# 14-DPLL_1.net
KiCad netlist of a schematic drawn in Altium Designer
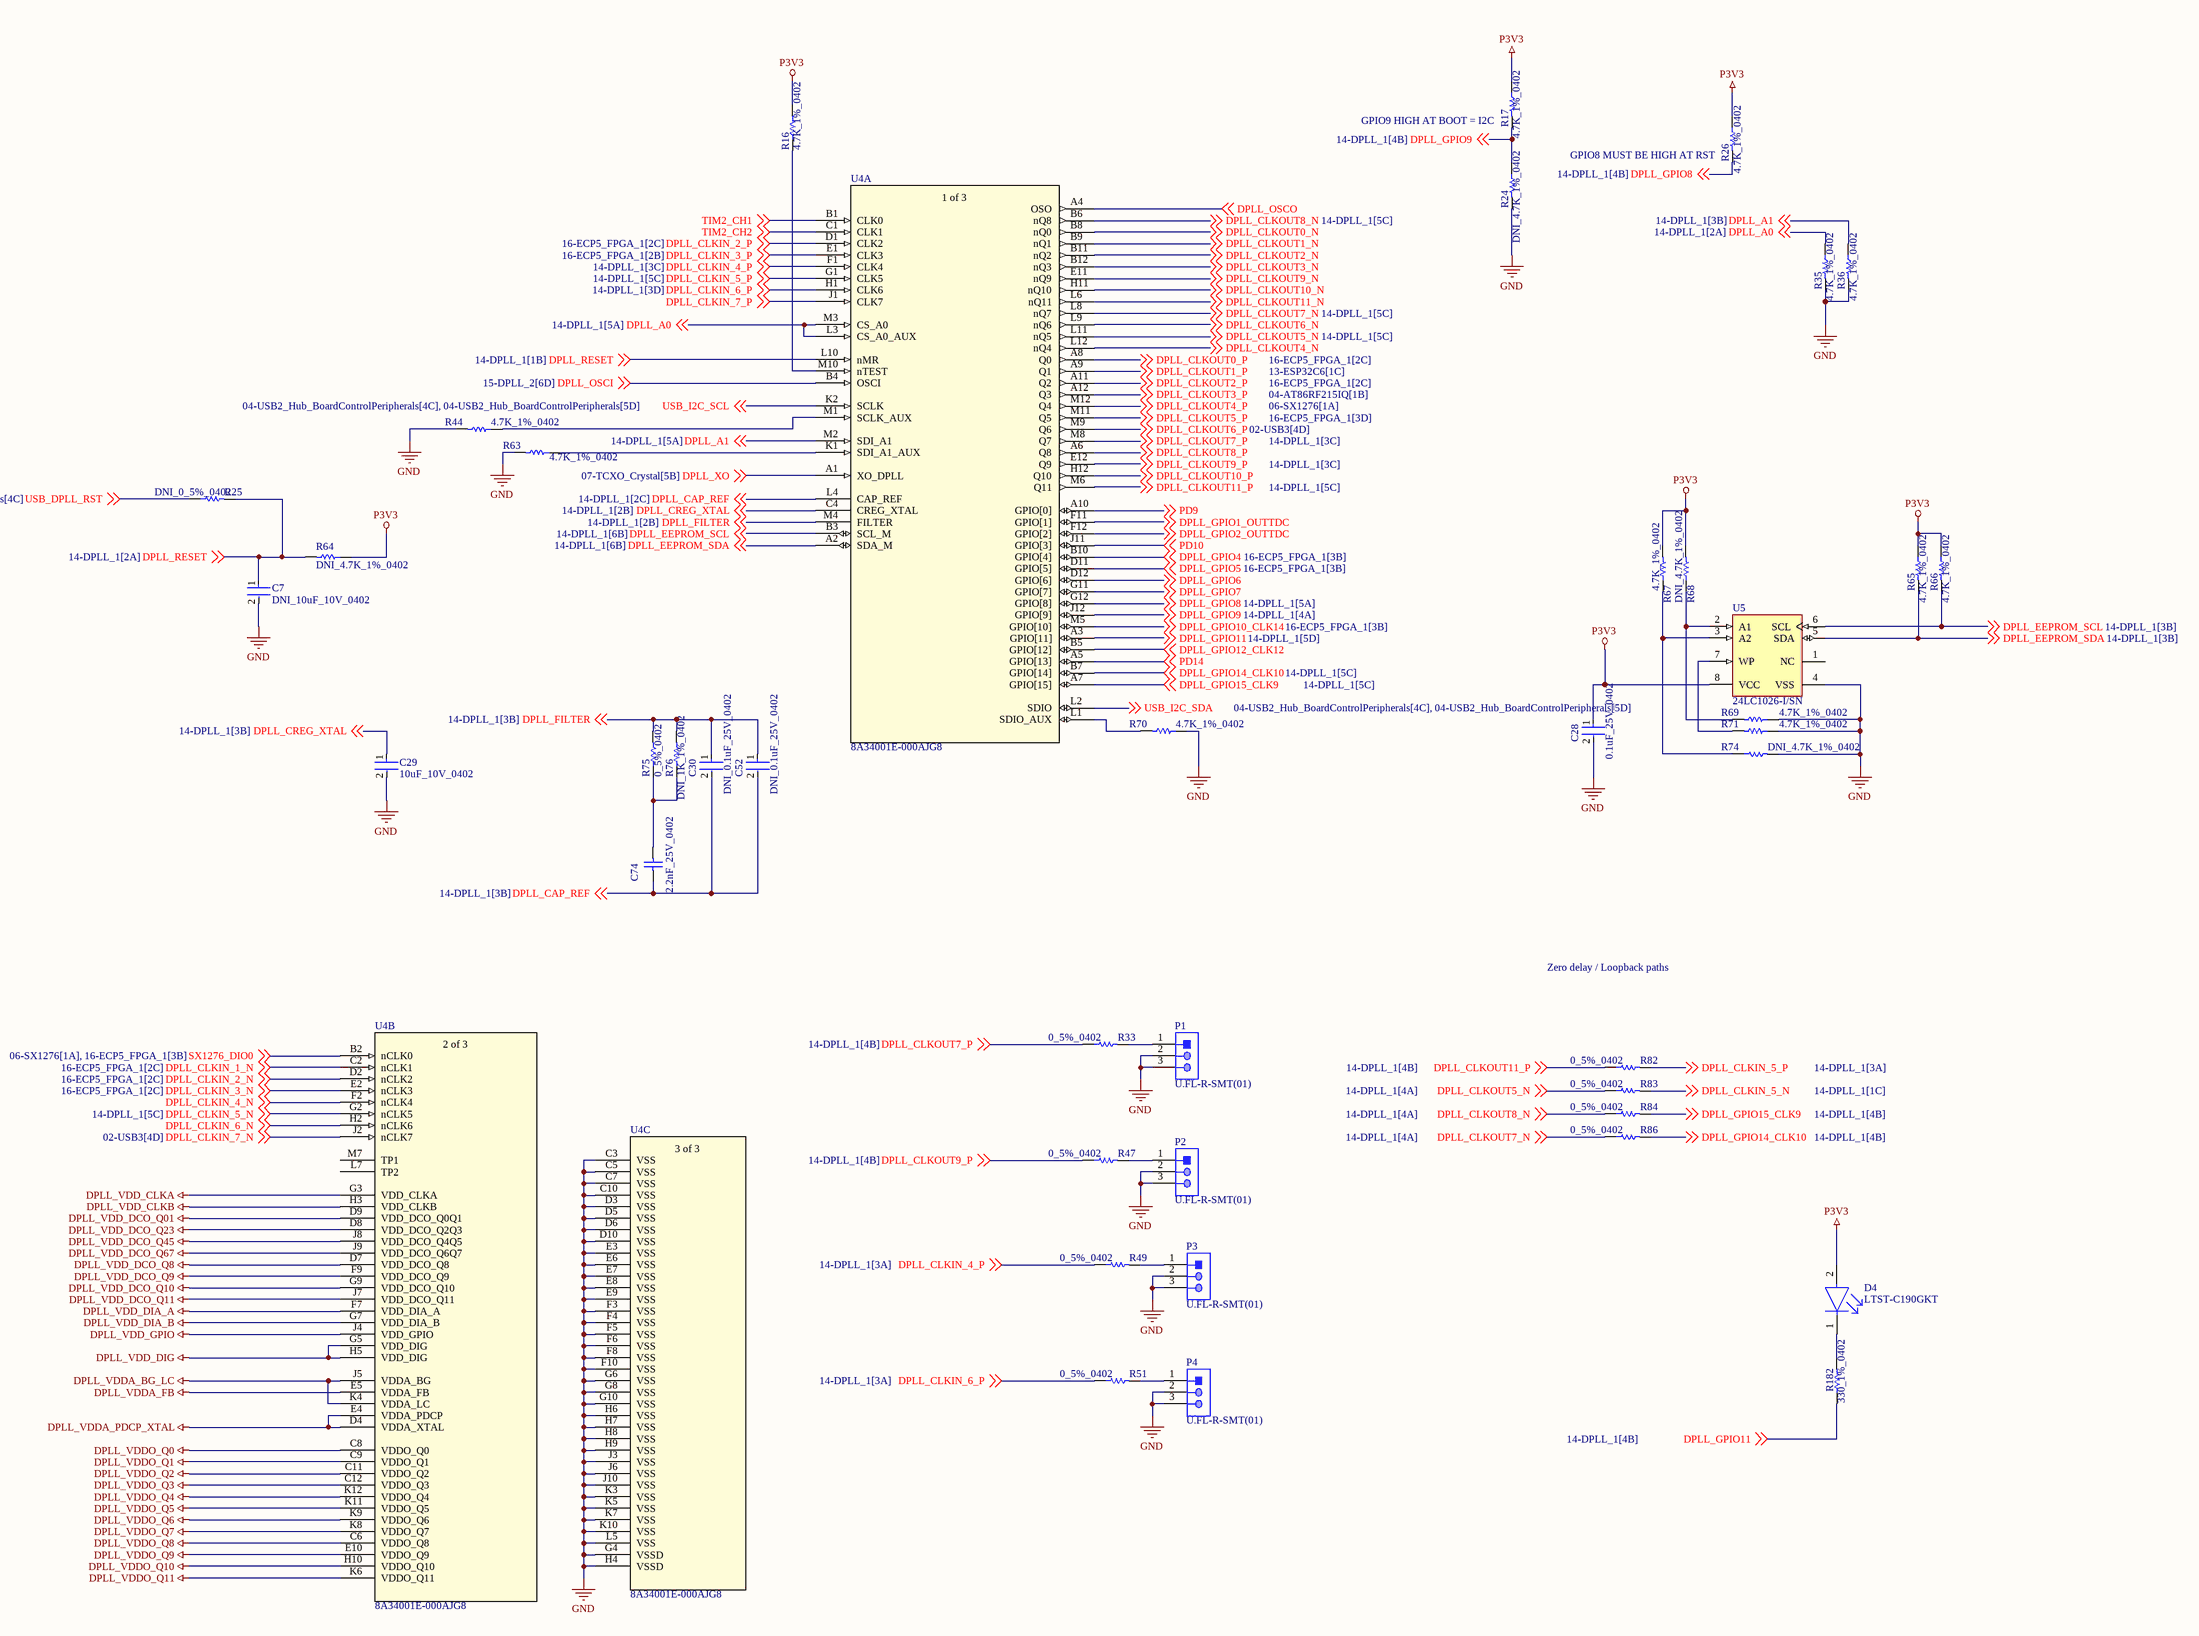
[diagram p0: 14-DPLL_1.SchDoc]

(export (version "E")
  (design (tool "Eeschema 10.0.6"))
  (components
    (comp (ref "C7")
      (value "DNI_10uF_10V_0402")
      (footprint "FP-CL05A106MP5NUNC-MFG")
      (description "CAP CER 10UF 10V X5R 0402")
      (fields
        (field (name "OCTOPART") "https://octopart.com/cl05a106mp5nunc-samsung-22457395")
        (field (name "TOLERANCE") "20%")
      )
      (libsource (lib "Altium Content Vault") (part "b4654b650e69147ec39a6b967a45e02"))
    )
    (comp (ref "C28")
      (value "0.1uF_25V_0402")
      (footprint "FP-0402-L_1_0_1-W_0_5_0_1-IPC_C")
      (description "General Purpose Ceramic Capacitor, 0402, 100nF, 10%, X7R, 15%, 25V")
      (fields (field (name "VOLTAGE") "25V") (field (name "TOLERANCE") "10%"))
      (libsource (lib "Altium Content Vault") (part "b4654b650e69147ec39a6b967a45e02"))
    )
    (comp (ref "C29")
      (value "10uF_10V_0402")
      (footprint "FP-CL05A106MP5NUNC-MFG")
      (description "CAP CER 10UF 10V X5R 0402")
      (fields
        (field (name "OCTOPART") "https://octopart.com/cl05a106mp5nunc-samsung-22457395")
        (field (name "TOLERANCE") "20%")
      )
      (libsource (lib "Altium Content Vault") (part "b4654b650e69147ec39a6b967a45e02"))
    )
    (comp (ref "C30")
      (value "DNI_0.1uF_25V_0402")
      (footprint "FP-0402-L_1_0_1-W_0_5_0_1-IPC_C")
      (description "General Purpose Ceramic Capacitor, 0402, 100nF, 10%, X7R, 15%, 25V")
      (fields (field (name "VOLTAGE") "25V") (field (name "TOLERANCE") "10%"))
      (libsource (lib "Altium Content Vault") (part "b4654b650e69147ec39a6b967a45e02"))
    )
    (comp (ref "C52")
      (value "DNI_0.1uF_25V_0402")
      (footprint "FP-0402-L_1_0_1-W_0_5_0_1-IPC_C")
      (description "General Purpose Ceramic Capacitor, 0402, 100nF, 10%, X7R, 15%, 25V")
      (fields (field (name "VOLTAGE") "25V") (field (name "TOLERANCE") "10%"))
      (libsource (lib "Altium Content Vault") (part "b4654b650e69147ec39a6b967a45e02"))
    )
    (comp (ref "C74")
      (value "2.2nF_25V_0402")
      (footprint "CAPC1005X56X25LL10T15")
      (fields
        (field (name "MANUFACTURER") "AVX Interconnect / Elco")
        (field (name "PART NUMBER") "04025C222JAT2A")
      )
      (libsource (lib "Altium Content Vault") (part "CAP"))
    )
    (comp (ref "D4")
      (value "LTST-C190GKT")
      (footprint "FP-LTST-C190GKT-MFG")
      (description "LED GREEN CLEAR CHIP SMD")
      (fields (field (name "VOLTAGE") "2V"))
      (libsource (lib "Altium Content Vault") (part "8706943c75ba83719d021d2fdc84c58"))
    )
    (comp (ref "P1")
      (value "U.FL-R-SMT(01)")
      (footprint "HRS-U.FL-R-SMT(10)_V")
      (description "CONN RECPT ULTRA-MINI COAX SMD")
      (fields (field (name "MANUFACTURER") "Hirose Electric") (field (name "APPROVAL CATEGORY") "UL94V-0"))
      (libsource (lib "Altium Content Vault") (part "CN-1P-M-R3"))
    )
    (comp (ref "P2")
      (value "U.FL-R-SMT(01)")
      (footprint "HRS-U.FL-R-SMT(10)_V")
      (description "CONN RECPT ULTRA-MINI COAX SMD")
      (fields (field (name "MANUFACTURER") "Hirose Electric") (field (name "APPROVAL CATEGORY") "UL94V-0"))
      (libsource (lib "Altium Content Vault") (part "CN-1P-M-R3"))
    )
    (comp (ref "P3")
      (value "U.FL-R-SMT(01)")
      (footprint "HRS-U.FL-R-SMT(10)_V")
      (description "CONN RECPT ULTRA-MINI COAX SMD")
      (fields (field (name "MANUFACTURER") "Hirose Electric") (field (name "APPROVAL CATEGORY") "UL94V-0"))
      (libsource (lib "Altium Content Vault") (part "CN-1P-M-R3"))
    )
    (comp (ref "P4")
      (value "U.FL-R-SMT(01)")
      (footprint "HRS-U.FL-R-SMT(10)_V")
      (description "CONN RECPT ULTRA-MINI COAX SMD")
      (fields (field (name "MANUFACTURER") "Hirose Electric") (field (name "APPROVAL CATEGORY") "UL94V-0"))
      (libsource (lib "Altium Content Vault") (part "CN-1P-M-R3"))
    )
    (comp (ref "R16")
      (value "4.7K_1%_0402")
      (footprint "RESC1005X40X25NL10T10")
      (fields (field (name "MANUFACTURER") "Bourns") (field (name "PART NUMBER") "CR0402-FX-4701GLF"))
      (libsource (lib "Altium Content Vault") (part "RES"))
    )
    (comp (ref "R17")
      (value "4.7K_1%_0402")
      (footprint "RESC1005X40X25NL10T10")
      (fields (field (name "MANUFACTURER") "Bourns") (field (name "PART NUMBER") "CR0402-FX-4701GLF"))
      (libsource (lib "Altium Content Vault") (part "RES"))
    )
    (comp (ref "R24")
      (value "DNI_4.7K_1%_0402")
      (footprint "RESC1005X40X25NL10T10")
      (fields (field (name "MANUFACTURER") "Bourns") (field (name "PART NUMBER") "CR0402-FX-4701GLF"))
      (libsource (lib "Altium Content Vault") (part "RES"))
    )
    (comp (ref "R25")
      (value "DNI_0_5%_0402")
      (footprint "RESC1005X40X25LL10T10")
      (fields (field (name "MANUFACTURER") "KOA Speer") (field (name "PART NUMBER") "RK73Z1ETTP"))
      (libsource (lib "Altium Content Vault") (part "RES"))
    )
    (comp (ref "R26")
      (value "4.7K_1%_0402")
      (footprint "RESC1005X40X25NL10T10")
      (fields (field (name "MANUFACTURER") "Bourns") (field (name "PART NUMBER") "CR0402-FX-4701GLF"))
      (libsource (lib "Altium Content Vault") (part "RES"))
    )
    (comp (ref "R33")
      (value "0_5%_0402")
      (footprint "RESC1005X40X25LL10T10")
      (fields (field (name "MANUFACTURER") "KOA Speer") (field (name "PART NUMBER") "RK73Z1ETTP"))
      (libsource (lib "Altium Content Vault") (part "RES"))
    )
    (comp (ref "R35")
      (value "4.7K_1%_0402")
      (footprint "RESC1005X40X25NL10T10")
      (fields (field (name "MANUFACTURER") "Bourns") (field (name "PART NUMBER") "CR0402-FX-4701GLF"))
      (libsource (lib "Altium Content Vault") (part "RES"))
    )
    (comp (ref "R36")
      (value "4.7K_1%_0402")
      (footprint "RESC1005X40X25NL10T10")
      (fields (field (name "MANUFACTURER") "Bourns") (field (name "PART NUMBER") "CR0402-FX-4701GLF"))
      (libsource (lib "Altium Content Vault") (part "RES"))
    )
    (comp (ref "R44")
      (value "4.7K_1%_0402")
      (footprint "RESC1005X40X25NL10T10")
      (fields (field (name "MANUFACTURER") "Bourns") (field (name "PART NUMBER") "CR0402-FX-4701GLF"))
      (libsource (lib "Altium Content Vault") (part "RES"))
    )
    (comp (ref "R47")
      (value "0_5%_0402")
      (footprint "RESC1005X40X25LL10T10")
      (fields (field (name "MANUFACTURER") "KOA Speer") (field (name "PART NUMBER") "RK73Z1ETTP"))
      (libsource (lib "Altium Content Vault") (part "RES"))
    )
    (comp (ref "R49")
      (value "0_5%_0402")
      (footprint "RESC1005X40X25LL10T10")
      (fields (field (name "MANUFACTURER") "KOA Speer") (field (name "PART NUMBER") "RK73Z1ETTP"))
      (libsource (lib "Altium Content Vault") (part "RES"))
    )
    (comp (ref "R51")
      (value "0_5%_0402")
      (footprint "RESC1005X40X25LL10T10")
      (fields (field (name "MANUFACTURER") "KOA Speer") (field (name "PART NUMBER") "RK73Z1ETTP"))
      (libsource (lib "Altium Content Vault") (part "RES"))
    )
    (comp (ref "R63")
      (value "4.7K_1%_0402")
      (footprint "RESC1005X40X25NL10T10")
      (fields (field (name "MANUFACTURER") "Bourns") (field (name "PART NUMBER") "CR0402-FX-4701GLF"))
      (libsource (lib "Altium Content Vault") (part "RES"))
    )
    (comp (ref "R64")
      (value "DNI_4.7K_1%_0402")
      (footprint "RESC1005X40X25NL10T10")
      (fields (field (name "MANUFACTURER") "Bourns") (field (name "PART NUMBER") "CR0402-FX-4701GLF"))
      (libsource (lib "Altium Content Vault") (part "RES"))
    )
    (comp (ref "R65")
      (value "4.7K_1%_0402")
      (footprint "RESC1005X40X25NL10T10")
      (fields (field (name "MANUFACTURER") "Bourns") (field (name "PART NUMBER") "CR0402-FX-4701GLF"))
      (libsource (lib "Altium Content Vault") (part "RES"))
    )
    (comp (ref "R66")
      (value "4.7K_1%_0402")
      (footprint "RESC1005X40X25NL10T10")
      (fields (field (name "MANUFACTURER") "Bourns") (field (name "PART NUMBER") "CR0402-FX-4701GLF"))
      (libsource (lib "Altium Content Vault") (part "RES"))
    )
    (comp (ref "R67")
      (value "4.7K_1%_0402")
      (footprint "RESC1005X40X25NL10T10")
      (fields (field (name "MANUFACTURER") "Bourns") (field (name "PART NUMBER") "CR0402-FX-4701GLF"))
      (libsource (lib "Altium Content Vault") (part "RES"))
    )
    (comp (ref "R68")
      (value "DNI_4.7K_1%_0402")
      (footprint "RESC1005X40X25NL10T10")
      (fields (field (name "MANUFACTURER") "Bourns") (field (name "PART NUMBER") "CR0402-FX-4701GLF"))
      (libsource (lib "Altium Content Vault") (part "RES"))
    )
    (comp (ref "R69")
      (value "4.7K_1%_0402")
      (footprint "RESC1005X40X25NL10T10")
      (fields (field (name "MANUFACTURER") "Bourns") (field (name "PART NUMBER") "CR0402-FX-4701GLF"))
      (libsource (lib "Altium Content Vault") (part "RES"))
    )
    (comp (ref "R70")
      (value "4.7K_1%_0402")
      (footprint "RESC1005X40X25NL10T10")
      (fields (field (name "MANUFACTURER") "Bourns") (field (name "PART NUMBER") "CR0402-FX-4701GLF"))
      (libsource (lib "Altium Content Vault") (part "RES"))
    )
    (comp (ref "R71")
      (value "4.7K_1%_0402")
      (footprint "RESC1005X40X25NL10T10")
      (fields (field (name "MANUFACTURER") "Bourns") (field (name "PART NUMBER") "CR0402-FX-4701GLF"))
      (libsource (lib "Altium Content Vault") (part "RES"))
    )
    (comp (ref "R74")
      (value "DNI_4.7K_1%_0402")
      (footprint "RESC1005X40X25NL10T10")
      (fields (field (name "MANUFACTURER") "Bourns") (field (name "PART NUMBER") "CR0402-FX-4701GLF"))
      (libsource (lib "Altium Content Vault") (part "RES"))
    )
    (comp (ref "R75")
      (value "0_5%_0402")
      (footprint "RESC1005X40X25LL10T10")
      (fields (field (name "MANUFACTURER") "KOA Speer") (field (name "PART NUMBER") "RK73Z1ETTP"))
      (libsource (lib "Altium Content Vault") (part "RES"))
    )
    (comp (ref "R76")
      (value "DNI_1K_1%_0402")
      (footprint "RESC1005X40X25NL05T05")
      (fields (field (name "MANUFACTURER") "Vishay Dale") (field (name "PART NUMBER") "CRCW04021K00FKTD"))
      (libsource (lib "Altium Content Vault") (part "RES"))
    )
    (comp (ref "R82")
      (value "0_5%_0402")
      (footprint "RESC1005X40X25LL10T10")
      (fields (field (name "MANUFACTURER") "KOA Speer") (field (name "PART NUMBER") "RK73Z1ETTP"))
      (libsource (lib "Altium Content Vault") (part "RES"))
    )
    (comp (ref "R83")
      (value "0_5%_0402")
      (footprint "RESC1005X40X25LL10T10")
      (fields (field (name "MANUFACTURER") "KOA Speer") (field (name "PART NUMBER") "RK73Z1ETTP"))
      (libsource (lib "Altium Content Vault") (part "RES"))
    )
    (comp (ref "R84")
      (value "0_5%_0402")
      (footprint "RESC1005X40X25LL10T10")
      (fields (field (name "MANUFACTURER") "KOA Speer") (field (name "PART NUMBER") "RK73Z1ETTP"))
      (libsource (lib "Altium Content Vault") (part "RES"))
    )
    (comp (ref "R86")
      (value "0_5%_0402")
      (footprint "RESC1005X40X25LL10T10")
      (fields (field (name "MANUFACTURER") "KOA Speer") (field (name "PART NUMBER") "RK73Z1ETTP"))
      (libsource (lib "Altium Content Vault") (part "RES"))
    )
    (comp (ref "R182")
      (value "330_1%_0402")
      (footprint "RESC1005X40X25NL10T10")
      (fields (field (name "MANUFACTURER") "Panasonic") (field (name "PART NUMBER") "ERA-2AED331X"))
      (libsource (lib "Altium Content Vault") (part "RES"))
    )
    (comp (ref "U4")
      (value "8A34001E-000AJG8")
      (footprint "144-CABGA_REN")
      (description "No Description Available")
      (fields (field (name "COPYRIGHT") "Copyright (C) 2024 Ultra Librarian. All rights reserved."))
      (libsource (lib "8A34001E-000AJG8") (part "8A34001E-000AJG8"))
    )
    (comp (ref "U5")
      (value "24LC1026-I/SN")
      (footprint "MCHP-SOIC-SN8_N")
      (description "1024K bits I2C™ Serial EEPROM, 2.5 to 5.5 V, 400 kHz, -40 to 85 degC, 8-pin SOIC (SN8), Tube")
      (fields (field (name "MANUFACTURER") "Microchip"))
      (libsource (lib "Altium Content Vault") (part "MCHP-24LC1026-SOIC-8"))
    )
  )
  (nets
    (net (code "1") (name "DPLL_A0") (class "Default")
      (node (ref "R35") (pin "1") (pinfunction "1_1") (pintype "passive"))
      (node (ref "U4") (pin "L3") (pinfunction "CS_A0_AUX_L3") (pintype "input"))
      (node (ref "U4") (pin "M3") (pinfunction "CS_A0_M3") (pintype "input"))
    )
    (net (code "2") (name "DPLL_A1") (class "Default")
      (node (ref "R36") (pin "1") (pinfunction "1_1") (pintype "passive"))
      (node (ref "U4") (pin "M2") (pinfunction "SDI_A1_M2") (pintype "input"))
    )
    (net (code "3") (name "DPLL_CAP_REF") (class "Default")
      (node (ref "C30") (pin "2") (pinfunction "2_2") (pintype "passive"))
      (node (ref "C52") (pin "2") (pinfunction "2_2") (pintype "passive"))
      (node (ref "C74") (pin "1") (pinfunction "1_1") (pintype "passive"))
      (node (ref "U4") (pin "L4") (pinfunction "CAP_REF_L4") (pintype "passive"))
    )
    (net (code "4") (name "DPLL_CLKIN_1_N") (class "Default")
      (node (ref "U4") (pin "C2") (pinfunction "nCLK1_C2") (pintype "input"))
    )
    (net (code "5") (name "DPLL_CLKIN_2_N") (class "Default")
      (node (ref "U4") (pin "D2") (pinfunction "nCLK2_D2") (pintype "input"))
    )
    (net (code "6") (name "DPLL_CLKIN_2_P") (class "Default")
      (node (ref "U4") (pin "D1") (pinfunction "CLK2_D1") (pintype "input"))
    )
    (net (code "7") (name "DPLL_CLKIN_3_N") (class "Default")
      (node (ref "U4") (pin "E2") (pinfunction "nCLK3_E2") (pintype "input"))
    )
    (net (code "8") (name "DPLL_CLKIN_3_P") (class "Default")
      (node (ref "U4") (pin "E1") (pinfunction "CLK3_E1") (pintype "input"))
    )
    (net (code "9") (name "DPLL_CLKIN_4_N") (class "Default")
      (node (ref "U4") (pin "F2") (pinfunction "nCLK4_F2") (pintype "input"))
    )
    (net (code "10") (name "DPLL_CLKIN_4_P") (class "Default")
      (node (ref "R49") (pin "1") (pinfunction "1_1") (pintype "passive"))
      (node (ref "U4") (pin "F1") (pinfunction "CLK4_F1") (pintype "input"))
    )
    (net (code "11") (name "DPLL_CLKIN_5_N") (class "Default")
      (node (ref "R83") (pin "2") (pinfunction "2_2") (pintype "passive"))
      (node (ref "U4") (pin "G2") (pinfunction "nCLK5_G2") (pintype "input"))
    )
    (net (code "12") (name "DPLL_CLKIN_5_P") (class "Default")
      (node (ref "R82") (pin "2") (pinfunction "2_2") (pintype "passive"))
      (node (ref "U4") (pin "G1") (pinfunction "CLK5_G1") (pintype "input"))
    )
    (net (code "13") (name "DPLL_CLKIN_6_N") (class "Default")
      (node (ref "U4") (pin "H2") (pinfunction "nCLK6_H2") (pintype "input"))
    )
    (net (code "14") (name "DPLL_CLKIN_6_P") (class "Default")
      (node (ref "R51") (pin "1") (pinfunction "1_1") (pintype "passive"))
      (node (ref "U4") (pin "H1") (pinfunction "CLK6_H1") (pintype "input"))
    )
    (net (code "15") (name "DPLL_CLKIN_7_N") (class "Default")
      (node (ref "U4") (pin "J2") (pinfunction "nCLK7_J2") (pintype "input"))
    )
    (net (code "16") (name "DPLL_CLKIN_7_P") (class "Default")
      (node (ref "U4") (pin "J1") (pinfunction "CLK7_J1") (pintype "input"))
    )
    (net (code "17") (name "DPLL_CLKOUT0_N") (class "Default")
      (node (ref "U4") (pin "B8") (pinfunction "nQ0_B8") (pintype "output"))
    )
    (net (code "18") (name "DPLL_CLKOUT0_P") (class "Default")
      (node (ref "U4") (pin "A8") (pinfunction "Q0_A8") (pintype "output"))
    )
    (net (code "19") (name "DPLL_CLKOUT1_N") (class "Default")
      (node (ref "U4") (pin "B9") (pinfunction "nQ1_B9") (pintype "output"))
    )
    (net (code "20") (name "DPLL_CLKOUT1_P") (class "Default")
      (node (ref "U4") (pin "A9") (pinfunction "Q1_A9") (pintype "output"))
    )
    (net (code "21") (name "DPLL_CLKOUT2_N") (class "Default")
      (node (ref "U4") (pin "B11") (pinfunction "nQ2_B11") (pintype "output"))
    )
    (net (code "22") (name "DPLL_CLKOUT2_P") (class "Default")
      (node (ref "U4") (pin "A11") (pinfunction "Q2_A11") (pintype "output"))
    )
    (net (code "23") (name "DPLL_CLKOUT3_N") (class "Default")
      (node (ref "U4") (pin "B12") (pinfunction "nQ3_B12") (pintype "output"))
    )
    (net (code "24") (name "DPLL_CLKOUT3_P") (class "Default")
      (node (ref "U4") (pin "A12") (pinfunction "Q3_A12") (pintype "output"))
    )
    (net (code "25") (name "DPLL_CLKOUT4_N") (class "Default")
      (node (ref "U4") (pin "L12") (pinfunction "nQ4_L12") (pintype "output"))
    )
    (net (code "26") (name "DPLL_CLKOUT4_P") (class "Default")
      (node (ref "U4") (pin "M12") (pinfunction "Q4_M12") (pintype "output"))
    )
    (net (code "27") (name "DPLL_CLKOUT5_N") (class "Default")
      (node (ref "R83") (pin "1") (pinfunction "1_1") (pintype "passive"))
      (node (ref "U4") (pin "L11") (pinfunction "nQ5_L11") (pintype "output"))
    )
    (net (code "28") (name "DPLL_CLKOUT5_P") (class "Default")
      (node (ref "U4") (pin "M11") (pinfunction "Q5_M11") (pintype "output"))
    )
    (net (code "29") (name "DPLL_CLKOUT6_N") (class "Default")
      (node (ref "U4") (pin "L9") (pinfunction "nQ6_L9") (pintype "output"))
    )
    (net (code "30") (name "DPLL_CLKOUT6_P") (class "Default")
      (node (ref "U4") (pin "M9") (pinfunction "Q6_M9") (pintype "output"))
    )
    (net (code "31") (name "DPLL_CLKOUT7_N") (class "Default")
      (node (ref "R86") (pin "1") (pinfunction "1_1") (pintype "passive"))
      (node (ref "U4") (pin "L8") (pinfunction "nQ7_L8") (pintype "output"))
    )
    (net (code "32") (name "DPLL_CLKOUT7_P") (class "Default")
      (node (ref "R33") (pin "1") (pinfunction "1_1") (pintype "passive"))
      (node (ref "U4") (pin "M8") (pinfunction "Q7_M8") (pintype "output"))
    )
    (net (code "33") (name "DPLL_CLKOUT8_N") (class "Default")
      (node (ref "R84") (pin "1") (pinfunction "1_1") (pintype "passive"))
      (node (ref "U4") (pin "B6") (pinfunction "nQ8_B6") (pintype "output"))
    )
    (net (code "34") (name "DPLL_CLKOUT8_P") (class "Default")
      (node (ref "U4") (pin "A6") (pinfunction "Q8_A6") (pintype "output"))
    )
    (net (code "35") (name "DPLL_CLKOUT9_N") (class "Default")
      (node (ref "U4") (pin "E11") (pinfunction "nQ9_E11") (pintype "output"))
    )
    (net (code "36") (name "DPLL_CLKOUT9_P") (class "Default")
      (node (ref "R47") (pin "1") (pinfunction "1_1") (pintype "passive"))
      (node (ref "U4") (pin "E12") (pinfunction "Q9_E12") (pintype "output"))
    )
    (net (code "37") (name "DPLL_CLKOUT10_N") (class "Default")
      (node (ref "U4") (pin "H11") (pinfunction "nQ10_H11") (pintype "output"))
    )
    (net (code "38") (name "DPLL_CLKOUT10_P") (class "Default")
      (node (ref "U4") (pin "H12") (pinfunction "Q10_H12") (pintype "output"))
    )
    (net (code "39") (name "DPLL_CLKOUT11_N") (class "Default")
      (node (ref "U4") (pin "L6") (pinfunction "nQ11_L6") (pintype "output"))
    )
    (net (code "40") (name "DPLL_CLKOUT11_P") (class "Default")
      (node (ref "R82") (pin "1") (pinfunction "1_1") (pintype "passive"))
      (node (ref "U4") (pin "M6") (pinfunction "Q11_M6") (pintype "output"))
    )
    (net (code "41") (name "DPLL_CREG_XTAL") (class "Default")
      (node (ref "C29") (pin "1") (pinfunction "1_1") (pintype "passive"))
      (node (ref "U4") (pin "C4") (pinfunction "CREG_XTAL_C4") (pintype "passive"))
    )
    (net (code "42") (name "DPLL_EEPROM_SCL") (class "Default")
      (node (ref "R66") (pin "2") (pinfunction "2_2") (pintype "passive"))
      (node (ref "U4") (pin "B3") (pinfunction "SCL_M_B3") (pintype "bidirectional"))
      (node (ref "U5") (pin "6") (pinfunction "SCL_6") (pintype "input"))
    )
    (net (code "43") (name "DPLL_EEPROM_SDA") (class "Default")
      (node (ref "R65") (pin "2") (pinfunction "2_2") (pintype "passive"))
      (node (ref "U4") (pin "A2") (pinfunction "SDA_M_A2") (pintype "bidirectional"))
      (node (ref "U5") (pin "5") (pinfunction "SDA_5") (pintype "bidirectional"))
    )
    (net (code "44") (name "DPLL_FILTER") (class "Default")
      (node (ref "C30") (pin "1") (pinfunction "1_1") (pintype "passive"))
      (node (ref "C52") (pin "1") (pinfunction "1_1") (pintype "passive"))
      (node (ref "R75") (pin "2") (pinfunction "2_2") (pintype "passive"))
      (node (ref "R76") (pin "2") (pinfunction "2_2") (pintype "passive"))
      (node (ref "U4") (pin "M4") (pinfunction "FILTER_M4") (pintype "passive"))
    )
    (net (code "45") (name "DPLL_GPIO1_OUTTDC") (class "Default")
      (node (ref "U4") (pin "F11") (pinfunction "GPIO[1]_F11") (pintype "bidirectional"))
    )
    (net (code "46") (name "DPLL_GPIO2_OUTTDC") (class "Default")
      (node (ref "U4") (pin "F12") (pinfunction "GPIO[2]_F12") (pintype "bidirectional"))
    )
    (net (code "47") (name "DPLL_GPIO4") (class "Default")
      (node (ref "U4") (pin "B10") (pinfunction "GPIO[4]_B10") (pintype "bidirectional"))
    )
    (net (code "48") (name "DPLL_GPIO5") (class "Default")
      (node (ref "U4") (pin "D11") (pinfunction "GPIO[5]_D11") (pintype "bidirectional"))
    )
    (net (code "49") (name "DPLL_GPIO6") (class "Default")
      (node (ref "U4") (pin "D12") (pinfunction "GPIO[6]_D12") (pintype "bidirectional"))
    )
    (net (code "50") (name "DPLL_GPIO7") (class "Default")
      (node (ref "U4") (pin "G11") (pinfunction "GPIO[7]_G11") (pintype "bidirectional"))
    )
    (net (code "51") (name "DPLL_GPIO8") (class "Default")
      (node (ref "R26") (pin "2") (pinfunction "2_2") (pintype "passive"))
      (node (ref "U4") (pin "G12") (pinfunction "GPIO[8]_G12") (pintype "bidirectional"))
    )
    (net (code "52") (name "DPLL_GPIO9") (class "Default")
      (node (ref "R17") (pin "2") (pinfunction "2_2") (pintype "passive"))
      (node (ref "R24") (pin "1") (pinfunction "1_1") (pintype "passive"))
      (node (ref "U4") (pin "J12") (pinfunction "GPIO[9]_J12") (pintype "bidirectional"))
    )
    (net (code "53") (name "DPLL_GPIO10_CLK14") (class "Default")
      (node (ref "U4") (pin "M5") (pinfunction "GPIO[10]_M5") (pintype "bidirectional"))
    )
    (net (code "54") (name "DPLL_GPIO11") (class "Default")
      (node (ref "R182") (pin "1") (pinfunction "1_1") (pintype "passive"))
      (node (ref "U4") (pin "A3") (pinfunction "GPIO[11]_A3") (pintype "bidirectional"))
    )
    (net (code "55") (name "DPLL_GPIO12_CLK12") (class "Default")
      (node (ref "U4") (pin "B5") (pinfunction "GPIO[12]_B5") (pintype "bidirectional"))
    )
    (net (code "56") (name "DPLL_GPIO14_CLK10") (class "Default")
      (node (ref "R86") (pin "2") (pinfunction "2_2") (pintype "passive"))
      (node (ref "U4") (pin "B7") (pinfunction "GPIO[14]_B7") (pintype "bidirectional"))
    )
    (net (code "57") (name "DPLL_GPIO15_CLK9") (class "Default")
      (node (ref "R84") (pin "2") (pinfunction "2_2") (pintype "passive"))
      (node (ref "U4") (pin "A7") (pinfunction "GPIO[15]_A7") (pintype "bidirectional"))
    )
    (net (code "58") (name "DPLL_OSCI") (class "Default")
      (node (ref "U4") (pin "B4") (pinfunction "OSCI_B4") (pintype "input"))
    )
    (net (code "59") (name "DPLL_OSCO") (class "Default")
      (node (ref "U4") (pin "A4") (pinfunction "OSO_A4") (pintype "output"))
    )
    (net (code "60") (name "DPLL_RESET") (class "Default")
      (node (ref "C7") (pin "1") (pinfunction "1_1") (pintype "passive"))
      (node (ref "R25") (pin "2") (pinfunction "2_2") (pintype "passive"))
      (node (ref "R64") (pin "2") (pinfunction "2_2") (pintype "passive"))
      (node (ref "U4") (pin "L10") (pinfunction "nMR_L10") (pintype "input"))
    )
    (net (code "61") (name "DPLL_VDDA_BG_LC") (class "Default")
      (node (ref "U4") (pin "J5") (pinfunction "VDDA_BG_J5") (pintype "power_in"))
      (node (ref "U4") (pin "K4") (pinfunction "VDDA_LC_K4") (pintype "power_in"))
    )
    (net (code "62") (name "DPLL_VDDA_FB") (class "Default")
      (node (ref "U4") (pin "E5") (pinfunction "VDDA_FB_E5") (pintype "power_in"))
    )
    (net (code "63") (name "DPLL_VDDA_PDCP_XTAL") (class "Default")
      (node (ref "U4") (pin "D4") (pinfunction "VDDA_XTAL_D4") (pintype "power_in"))
      (node (ref "U4") (pin "E4") (pinfunction "VDDA_PDCP_E4") (pintype "power_in"))
    )
    (net (code "64") (name "DPLL_VDDO_Q0") (class "Default")
      (node (ref "U4") (pin "C8") (pinfunction "VDDO_Q0_C8") (pintype "power_in"))
    )
    (net (code "65") (name "DPLL_VDDO_Q1") (class "Default")
      (node (ref "U4") (pin "C9") (pinfunction "VDDO_Q1_C9") (pintype "power_in"))
    )
    (net (code "66") (name "DPLL_VDDO_Q2") (class "Default")
      (node (ref "U4") (pin "C11") (pinfunction "VDDO_Q2_C11") (pintype "power_in"))
    )
    (net (code "67") (name "DPLL_VDDO_Q3") (class "Default")
      (node (ref "U4") (pin "C12") (pinfunction "VDDO_Q3_C12") (pintype "power_in"))
    )
    (net (code "68") (name "DPLL_VDDO_Q4") (class "Default")
      (node (ref "U4") (pin "K12") (pinfunction "VDDO_Q4_K12") (pintype "power_in"))
    )
    (net (code "69") (name "DPLL_VDDO_Q5") (class "Default")
      (node (ref "U4") (pin "K11") (pinfunction "VDDO_Q5_K11") (pintype "power_in"))
    )
    (net (code "70") (name "DPLL_VDDO_Q6") (class "Default")
      (node (ref "U4") (pin "K9") (pinfunction "VDDO_Q6_K9") (pintype "power_in"))
    )
    (net (code "71") (name "DPLL_VDDO_Q7") (class "Default")
      (node (ref "U4") (pin "K8") (pinfunction "VDDO_Q7_K8") (pintype "power_in"))
    )
    (net (code "72") (name "DPLL_VDDO_Q8") (class "Default")
      (node (ref "U4") (pin "C6") (pinfunction "VDDO_Q8_C6") (pintype "power_in"))
    )
    (net (code "73") (name "DPLL_VDDO_Q9") (class "Default")
      (node (ref "U4") (pin "E10") (pinfunction "VDDO_Q9_E10") (pintype "power_in"))
    )
    (net (code "74") (name "DPLL_VDDO_Q10") (class "Default")
      (node (ref "U4") (pin "H10") (pinfunction "VDDO_Q10_H10") (pintype "power_in"))
    )
    (net (code "75") (name "DPLL_VDDO_Q11") (class "Default")
      (node (ref "U4") (pin "K6") (pinfunction "VDDO_Q11_K6") (pintype "power_in"))
    )
    (net (code "76") (name "DPLL_VDD_CLKA") (class "Default")
      (node (ref "U4") (pin "G3") (pinfunction "VDD_CLKA_G3") (pintype "power_in"))
    )
    (net (code "77") (name "DPLL_VDD_CLKB") (class "Default")
      (node (ref "U4") (pin "H3") (pinfunction "VDD_CLKB_H3") (pintype "power_in"))
    )
    (net (code "78") (name "DPLL_VDD_DCO_Q01") (class "Default")
      (node (ref "U4") (pin "D9") (pinfunction "VDD_DCO_Q0Q1_D9") (pintype "power_in"))
    )
    (net (code "79") (name "DPLL_VDD_DCO_Q8") (class "Default")
      (node (ref "U4") (pin "D7") (pinfunction "VDD_DCO_Q8_D7") (pintype "power_in"))
    )
    (net (code "80") (name "DPLL_VDD_DCO_Q9") (class "Default")
      (node (ref "U4") (pin "F9") (pinfunction "VDD_DCO_Q9_F9") (pintype "power_in"))
    )
    (net (code "81") (name "DPLL_VDD_DCO_Q10") (class "Default")
      (node (ref "U4") (pin "G9") (pinfunction "VDD_DCO_Q10_G9") (pintype "power_in"))
    )
    (net (code "82") (name "DPLL_VDD_DCO_Q11") (class "Default")
      (node (ref "U4") (pin "J7") (pinfunction "VDD_DCO_Q11_J7") (pintype "power_in"))
    )
    (net (code "83") (name "DPLL_VDD_DCO_Q23") (class "Default")
      (node (ref "U4") (pin "D8") (pinfunction "VDD_DCO_Q2Q3_D8") (pintype "power_in"))
    )
    (net (code "84") (name "DPLL_VDD_DCO_Q45") (class "Default")
      (node (ref "U4") (pin "J8") (pinfunction "VDD_DCO_Q4Q5_J8") (pintype "power_in"))
    )
    (net (code "85") (name "DPLL_VDD_DCO_Q67") (class "Default")
      (node (ref "U4") (pin "J9") (pinfunction "VDD_DCO_Q6Q7_J9") (pintype "power_in"))
    )
    (net (code "86") (name "DPLL_VDD_DIA_A") (class "Default")
      (node (ref "U4") (pin "F7") (pinfunction "VDD_DIA_A_F7") (pintype "power_in"))
    )
    (net (code "87") (name "DPLL_VDD_DIA_B") (class "Default")
      (node (ref "U4") (pin "G7") (pinfunction "VDD_DIA_B_G7") (pintype "power_in"))
    )
    (net (code "88") (name "DPLL_VDD_DIG") (class "Default")
      (node (ref "U4") (pin "G5") (pinfunction "VDD_DIG_G5") (pintype "power_in"))
      (node (ref "U4") (pin "H5") (pinfunction "VDD_DIG_H5") (pintype "power_in"))
    )
    (net (code "89") (name "DPLL_VDD_GPIO") (class "Default")
      (node (ref "U4") (pin "J4") (pinfunction "VDD_GPIO_J4") (pintype "power_in"))
    )
    (net (code "90") (name "DPLL_XO") (class "Default")
      (node (ref "U4") (pin "A1") (pinfunction "XO_DPLL_A1") (pintype "input"))
    )
    (net (code "91") (name "GND") (class "Default")
      (node (ref "C28") (pin "2") (pinfunction "2_2") (pintype "passive"))
      (node (ref "C29") (pin "2") (pinfunction "2_2") (pintype "passive"))
      (node (ref "C7") (pin "2") (pinfunction "2_2") (pintype "passive"))
      (node (ref "P1") (pin "2") (pinfunction "2_2") (pintype "passive"))
      (node (ref "P1") (pin "3") (pinfunction "3_3") (pintype "passive"))
      (node (ref "P2") (pin "2") (pinfunction "2_2") (pintype "passive"))
      (node (ref "P2") (pin "3") (pinfunction "3_3") (pintype "passive"))
      (node (ref "P3") (pin "2") (pinfunction "2_2") (pintype "passive"))
      (node (ref "P3") (pin "3") (pinfunction "3_3") (pintype "passive"))
      (node (ref "P4") (pin "2") (pinfunction "2_2") (pintype "passive"))
      (node (ref "P4") (pin "3") (pinfunction "3_3") (pintype "passive"))
      (node (ref "R24") (pin "2") (pinfunction "2_2") (pintype "passive"))
      (node (ref "R35") (pin "2") (pinfunction "2_2") (pintype "passive"))
      (node (ref "R36") (pin "2") (pinfunction "2_2") (pintype "passive"))
      (node (ref "R44") (pin "2") (pinfunction "2_2") (pintype "passive"))
      (node (ref "R63") (pin "2") (pinfunction "2_2") (pintype "passive"))
      (node (ref "R69") (pin "1") (pinfunction "1_1") (pintype "passive"))
      (node (ref "R70") (pin "1") (pinfunction "1_1") (pintype "passive"))
      (node (ref "R71") (pin "1") (pinfunction "1_1") (pintype "passive"))
      (node (ref "R74") (pin "2") (pinfunction "2_2") (pintype "passive"))
      (node (ref "U4") (pin "C10") (pinfunction "VSS_C10") (pintype "power_in"))
      (node (ref "U4") (pin "C3") (pinfunction "VSS_C3") (pintype "power_in"))
      (node (ref "U4") (pin "C5") (pinfunction "VSS_C5") (pintype "power_in"))
      (node (ref "U4") (pin "C7") (pinfunction "VSS_C7") (pintype "power_in"))
      (node (ref "U4") (pin "D10") (pinfunction "VSS_D10") (pintype "power_in"))
      (node (ref "U4") (pin "D3") (pinfunction "VSS_D3") (pintype "power_in"))
      (node (ref "U4") (pin "D5") (pinfunction "VSS_D5") (pintype "power_in"))
      (node (ref "U4") (pin "D6") (pinfunction "VSS_D6") (pintype "power_in"))
      (node (ref "U4") (pin "E3") (pinfunction "VSS_E3") (pintype "power_in"))
      (node (ref "U4") (pin "E6") (pinfunction "VSS_E6") (pintype "power_in"))
      (node (ref "U4") (pin "E7") (pinfunction "VSS_E7") (pintype "power_in"))
      (node (ref "U4") (pin "E8") (pinfunction "VSS_E8") (pintype "power_in"))
      (node (ref "U4") (pin "E9") (pinfunction "VSS_E9") (pintype "power_in"))
      (node (ref "U4") (pin "F10") (pinfunction "VSS_F10") (pintype "power_in"))
      (node (ref "U4") (pin "F3") (pinfunction "VSS_F3") (pintype "power_in"))
      (node (ref "U4") (pin "F4") (pinfunction "VSS_F4") (pintype "power_in"))
      (node (ref "U4") (pin "F5") (pinfunction "VSS_F5") (pintype "power_in"))
      (node (ref "U4") (pin "F6") (pinfunction "VSS_F6") (pintype "power_in"))
      (node (ref "U4") (pin "F8") (pinfunction "VSS_F8") (pintype "power_in"))
      (node (ref "U4") (pin "G10") (pinfunction "VSS_G10") (pintype "power_in"))
      (node (ref "U4") (pin "G4") (pinfunction "VSSD_G4") (pintype "power_in"))
      (node (ref "U4") (pin "G6") (pinfunction "VSS_G6") (pintype "power_in"))
      (node (ref "U4") (pin "G8") (pinfunction "VSS_G8") (pintype "power_in"))
      (node (ref "U4") (pin "H4") (pinfunction "VSSD_H4") (pintype "power_in"))
      (node (ref "U4") (pin "H6") (pinfunction "VSS_H6") (pintype "power_in"))
      (node (ref "U4") (pin "H7") (pinfunction "VSS_H7") (pintype "power_in"))
      (node (ref "U4") (pin "H8") (pinfunction "VSS_H8") (pintype "power_in"))
      (node (ref "U4") (pin "H9") (pinfunction "VSS_H9") (pintype "power_in"))
      (node (ref "U4") (pin "J10") (pinfunction "VSS_J10") (pintype "power_in"))
      (node (ref "U4") (pin "J3") (pinfunction "VSS_J3") (pintype "power_in"))
      (node (ref "U4") (pin "J6") (pinfunction "VSS_J6") (pintype "power_in"))
      (node (ref "U4") (pin "K10") (pinfunction "VSS_K10") (pintype "power_in"))
      (node (ref "U4") (pin "K3") (pinfunction "VSS_K3") (pintype "power_in"))
      (node (ref "U4") (pin "K5") (pinfunction "VSS_K5") (pintype "power_in"))
      (node (ref "U4") (pin "K7") (pinfunction "VSS_K7") (pintype "power_in"))
      (node (ref "U4") (pin "L5") (pinfunction "VSS_L5") (pintype "power_in"))
      (node (ref "U5") (pin "4") (pinfunction "VSS_4") (pintype "power_in"))
    )
    (net (code "92") (name "Net-(C74-Pad2)") (class "Default")
      (node (ref "C74") (pin "2") (pinfunction "2_2") (pintype "passive"))
      (node (ref "R75") (pin "1") (pinfunction "1_1") (pintype "passive"))
      (node (ref "R76") (pin "1") (pinfunction "1_1") (pintype "passive"))
    )
    (net (code "93") (name "Net-(D4-C)") (class "Default")
      (node (ref "D4") (pin "1") (pinfunction "C_1") (pintype "passive"))
      (node (ref "R182") (pin "2") (pinfunction "2_2") (pintype "passive"))
    )
    (net (code "94") (name "Net-(P1-Pad1)") (class "Default")
      (node (ref "P1") (pin "1") (pinfunction "1_1") (pintype "passive"))
      (node (ref "R33") (pin "2") (pinfunction "2_2") (pintype "passive"))
    )
    (net (code "95") (name "Net-(P2-Pad1)") (class "Default")
      (node (ref "P2") (pin "1") (pinfunction "1_1") (pintype "passive"))
      (node (ref "R47") (pin "2") (pinfunction "2_2") (pintype "passive"))
    )
    (net (code "96") (name "Net-(P3-Pad1)") (class "Default")
      (node (ref "P3") (pin "1") (pinfunction "1_1") (pintype "passive"))
      (node (ref "R49") (pin "2") (pinfunction "2_2") (pintype "passive"))
    )
    (net (code "97") (name "Net-(P4-Pad1)") (class "Default")
      (node (ref "P4") (pin "1") (pinfunction "1_1") (pintype "passive"))
      (node (ref "R51") (pin "2") (pinfunction "2_2") (pintype "passive"))
    )
    (net (code "98") (name "Net-(U4A-SCLK_AUX)") (class "Default")
      (node (ref "R44") (pin "1") (pinfunction "1_1") (pintype "passive"))
      (node (ref "U4") (pin "M1") (pinfunction "SCLK_AUX_M1") (pintype "input"))
    )
    (net (code "99") (name "Net-(U4A-SDIO_AUX)") (class "Default")
      (node (ref "R70") (pin "2") (pinfunction "2_2") (pintype "passive"))
      (node (ref "U4") (pin "L1") (pinfunction "SDIO_AUX_L1") (pintype "bidirectional"))
    )
    (net (code "100") (name "Net-(U4A-SDI_A1_AUX)") (class "Default")
      (node (ref "R63") (pin "1") (pinfunction "1_1") (pintype "passive"))
      (node (ref "U4") (pin "K1") (pinfunction "SDI_A1_AUX_K1") (pintype "input"))
    )
    (net (code "101") (name "Net-(U4A-nTEST)") (class "Default")
      (node (ref "R16") (pin "1") (pinfunction "1_1") (pintype "passive"))
      (node (ref "U4") (pin "M10") (pinfunction "nTEST_M10") (pintype "input"))
    )
    (net (code "102") (name "Net-(U5-A1)") (class "Default")
      (node (ref "R68") (pin "1") (pinfunction "1_1") (pintype "passive"))
      (node (ref "R69") (pin "2") (pinfunction "2_2") (pintype "passive"))
      (node (ref "U5") (pin "2") (pinfunction "A1_2") (pintype "input"))
    )
    (net (code "103") (name "Net-(U5-A2)") (class "Default")
      (node (ref "R67") (pin "1") (pinfunction "1_1") (pintype "passive"))
      (node (ref "R74") (pin "1") (pinfunction "1_1") (pintype "passive"))
      (node (ref "U5") (pin "3") (pinfunction "A2_3") (pintype "input"))
    )
    (net (code "104") (name "Net-(U5-WP)") (class "Default")
      (node (ref "R71") (pin "2") (pinfunction "2_2") (pintype "passive"))
      (node (ref "U5") (pin "7") (pinfunction "WP_7") (pintype "input"))
    )
    (net (code "105") (name "P3V3") (class "Default")
      (node (ref "C28") (pin "1") (pinfunction "1_1") (pintype "passive"))
      (node (ref "D4") (pin "2") (pinfunction "A_2") (pintype "passive"))
      (node (ref "R16") (pin "2") (pinfunction "2_2") (pintype "passive"))
      (node (ref "R17") (pin "1") (pinfunction "1_1") (pintype "passive"))
      (node (ref "R26") (pin "1") (pinfunction "1_1") (pintype "passive"))
      (node (ref "R64") (pin "1") (pinfunction "1_1") (pintype "passive"))
      (node (ref "R65") (pin "1") (pinfunction "1_1") (pintype "passive"))
      (node (ref "R66") (pin "1") (pinfunction "1_1") (pintype "passive"))
      (node (ref "R67") (pin "2") (pinfunction "2_2") (pintype "passive"))
      (node (ref "R68") (pin "2") (pinfunction "2_2") (pintype "passive"))
      (node (ref "U5") (pin "8") (pinfunction "VCC_8") (pintype "power_in"))
    )
    (net (code "106") (name "PD9") (class "Default")
      (node (ref "U4") (pin "A10") (pinfunction "GPIO[0]_A10") (pintype "bidirectional"))
    )
    (net (code "107") (name "PD10") (class "Default")
      (node (ref "U4") (pin "J11") (pinfunction "GPIO[3]_J11") (pintype "bidirectional"))
    )
    (net (code "108") (name "PD14") (class "Default")
      (node (ref "U4") (pin "A5") (pinfunction "GPIO[13]_A5") (pintype "bidirectional"))
    )
    (net (code "109") (name "SX1276_DIO0") (class "Default")
      (node (ref "U4") (pin "B2") (pinfunction "nCLK0_B2") (pintype "input"))
    )
    (net (code "110") (name "TIM2_CH1") (class "Default")
      (node (ref "U4") (pin "B1") (pinfunction "CLK0_B1") (pintype "input"))
    )
    (net (code "111") (name "TIM2_CH2") (class "Default")
      (node (ref "U4") (pin "C1") (pinfunction "CLK1_C1") (pintype "input"))
    )
    (net (code "112") (name "USB_DPLL_RST") (class "Default")
      (node (ref "R25") (pin "1") (pinfunction "1_1") (pintype "passive"))
    )
    (net (code "113") (name "USB_I2C_SCL") (class "Default")
      (node (ref "U4") (pin "K2") (pinfunction "SCLK_K2") (pintype "input"))
    )
    (net (code "114") (name "USB_I2C_SDA") (class "Default")
      (node (ref "U4") (pin "L2") (pinfunction "SDIO_L2") (pintype "bidirectional"))
    )
    (net (code "115") (name "unconnected-(U4B-TP1-PadM7)") (class "Default")
      (node (ref "U4") (pin "M7") (pinfunction "TP1_M7") (pintype "passive"))
    )
    (net (code "116") (name "unconnected-(U4B-TP2-PadL7)") (class "Default")
      (node (ref "U4") (pin "L7") (pinfunction "TP2_L7") (pintype "passive"))
    )
    (net (code "117") (name "unconnected-(U5-NC-Pad1)") (class "Default")
      (node (ref "U5") (pin "1") (pinfunction "NC_1") (pintype "passive"))
    )
  )
)
